# ExtensionBoard.net
KiCad netlist of a schematic drawn in EAGLE
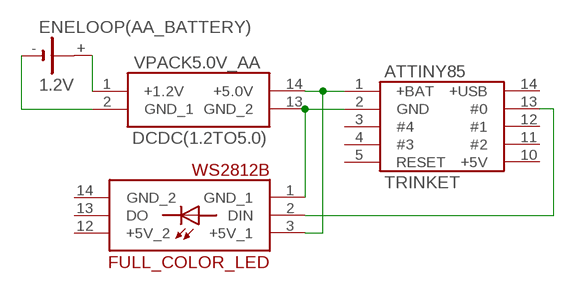
[diagram p0: schematic, sheet 1]

(export (version "E")
  (design (tool "Eeschema 10.0.6"))
  (components
    (comp (ref "ATTINY85")
      (value "TRINKET")
      (footprint "eagle-import:DIL10")
      (libsource (lib "eagle-import") (part "TRINKET"))
    )
    (comp (ref "ENELOOP(AA_BATTERY)")
      (value "1.2V")
      (footprint "eagle-import:1V60R")
      (libsource (lib "eagle-import") (part "1V60R"))
    )
    (comp (ref "VPACK5.0V_AA")
      (value "DCDC(1.2TO5.0)")
      (footprint "eagle-import:DIL4")
      (libsource (lib "eagle-import") (part "DCDC(1.2TO5.0)"))
    )
    (comp (ref "WS2812B")
      (value "FULL_COLOR_LED")
      (footprint "eagle-import:DIL6")
      (libsource (lib "eagle-import") (part "FULL_COLOR_LED"))
    )
  )
  (nets
    (net (code "1") (name "Net-(ATTINY85-#0)") (class "Default")
      (node (ref "ATTINY85") (pin "13") (pinfunction "#0_13") (pintype "bidirectional"))
      (node (ref "WS2812B") (pin "2") (pinfunction "DIN_2") (pintype "bidirectional"))
    )
    (net (code "2") (name "Net-(ATTINY85-+BAT)") (class "Default")
      (node (ref "ATTINY85") (pin "1") (pinfunction "+BAT_1") (pintype "bidirectional"))
      (node (ref "VPACK5.0V_AA") (pin "14") (pinfunction "+5.0V_14") (pintype "bidirectional"))
      (node (ref "WS2812B") (pin "3") (pinfunction "+5V_1_3") (pintype "bidirectional"))
    )
    (net (code "3") (name "Net-(ATTINY85-GND)") (class "Default")
      (node (ref "ATTINY85") (pin "2") (pinfunction "GND_2") (pintype "bidirectional"))
      (node (ref "VPACK5.0V_AA") (pin "13") (pinfunction "GND_2_13") (pintype "bidirectional"))
      (node (ref "WS2812B") (pin "1") (pinfunction "GND_1_1") (pintype "bidirectional"))
    )
    (net (code "4") (name "Net-(VPACK5.0V_AA-+1.2V)") (class "Default")
      (node (ref "ENELOOP(AA_BATTERY)") (pin "+") (pinfunction "+_+") (pintype "passive"))
      (node (ref "VPACK5.0V_AA") (pin "1") (pinfunction "+1.2V_1") (pintype "bidirectional"))
    )
    (net (code "5") (name "Net-(VPACK5.0V_AA-GND_1)") (class "Default")
      (node (ref "ENELOOP(AA_BATTERY)") (pin "-") (pinfunction "-_-") (pintype "passive"))
      (node (ref "VPACK5.0V_AA") (pin "2") (pinfunction "GND_1_2") (pintype "bidirectional"))
    )
    (net (code "6") (name "unconnected-(ATTINY85-#1-Pad12)") (class "Default")
      (node (ref "ATTINY85") (pin "12") (pinfunction "#1_12") (pintype "bidirectional"))
    )
    (net (code "7") (name "unconnected-(ATTINY85-#2-Pad11)") (class "Default")
      (node (ref "ATTINY85") (pin "11") (pinfunction "#2_11") (pintype "bidirectional"))
    )
    (net (code "8") (name "unconnected-(ATTINY85-#3-Pad4)") (class "Default")
      (node (ref "ATTINY85") (pin "4") (pinfunction "#3_4") (pintype "bidirectional"))
    )
    (net (code "9") (name "unconnected-(ATTINY85-#4-Pad3)") (class "Default")
      (node (ref "ATTINY85") (pin "3") (pinfunction "#4_3") (pintype "bidirectional"))
    )
    (net (code "10") (name "unconnected-(ATTINY85-+5V-Pad10)") (class "Default")
      (node (ref "ATTINY85") (pin "10") (pinfunction "+5V_10") (pintype "bidirectional"))
    )
    (net (code "11") (name "unconnected-(ATTINY85-+USB-Pad14)") (class "Default")
      (node (ref "ATTINY85") (pin "14") (pinfunction "+USB_14") (pintype "bidirectional"))
    )
    (net (code "12") (name "unconnected-(ATTINY85-RESET-Pad5)") (class "Default")
      (node (ref "ATTINY85") (pin "5") (pinfunction "RESET_5") (pintype "bidirectional"))
    )
    (net (code "13") (name "unconnected-(ENELOOP(AA_BATTERY)-+-Pad+@1)") (class "Default")
      (node (ref "ENELOOP(AA_BATTERY)") (pin "+@1") (pinfunction "+_+@1") (pintype "passive"))
    )
    (net (code "14") (name "unconnected-(WS2812B-+5V_2-Pad12)") (class "Default")
      (node (ref "WS2812B") (pin "12") (pinfunction "+5V_2_12") (pintype "bidirectional"))
    )
    (net (code "15") (name "unconnected-(WS2812B-DO-Pad13)") (class "Default")
      (node (ref "WS2812B") (pin "13") (pinfunction "DO_13") (pintype "bidirectional"))
    )
    (net (code "16") (name "unconnected-(WS2812B-GND_2-Pad14)") (class "Default")
      (node (ref "WS2812B") (pin "14") (pinfunction "GND_2_14") (pintype "bidirectional"))
    )
  )
)
